# Filter.net
KiCad netlist of a schematic drawn in Altium Designer
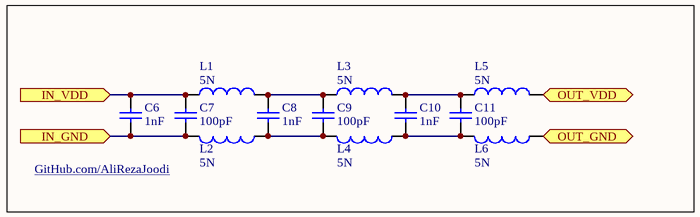
[diagram p0: Filter.SchDoc]

(export (version "E")
  (design (tool "Eeschema 10.0.6"))
  (components
    (comp (ref "C6")
      (value "1nF")
      (footprint "CAPNTO2.54-3.56x2.03")
      (description "Capacitor")
      (fields (field (name "MANUFACTURER") "Generic Components") (field (name "PUBLISHER") "Altium Limited"))
      (libsource (lib "Miscellaneous Devices") (part "Cap"))
    )
    (comp (ref "C7")
      (value "100pF")
      (footprint "CAPNTO2.54-3.56x2.03")
      (description "Capacitor")
      (fields (field (name "MANUFACTURER") "Generic Components") (field (name "PUBLISHER") "Altium Limited"))
      (libsource (lib "Miscellaneous Devices") (part "Cap"))
    )
    (comp (ref "C8")
      (value "1nF")
      (footprint "CAPNTO2.54-3.56x2.03")
      (description "Capacitor")
      (fields (field (name "MANUFACTURER") "Generic Components") (field (name "PUBLISHER") "Altium Limited"))
      (libsource (lib "Miscellaneous Devices") (part "Cap"))
    )
    (comp (ref "C9")
      (value "100pF")
      (footprint "CAPNTO2.54-3.56x2.03")
      (description "Capacitor")
      (fields (field (name "MANUFACTURER") "Generic Components") (field (name "PUBLISHER") "Altium Limited"))
      (libsource (lib "Miscellaneous Devices") (part "Cap"))
    )
    (comp (ref "C10")
      (value "1nF")
      (footprint "CAPNTO2.54-3.56x2.03")
      (description "Capacitor")
      (fields (field (name "MANUFACTURER") "Generic Components") (field (name "PUBLISHER") "Altium Limited"))
      (libsource (lib "Miscellaneous Devices") (part "Cap"))
    )
    (comp (ref "C11")
      (value "100pF")
      (footprint "CAPNTO2.54-3.56x2.03")
      (description "Capacitor")
      (fields (field (name "MANUFACTURER") "Generic Components") (field (name "PUBLISHER") "Altium Limited"))
      (libsource (lib "Miscellaneous Devices") (part "Cap"))
    )
    (comp (ref "L1")
      (value "5N")
      (footprint "CAPPR5-6.3x11")
      (description "Inductor")
      (fields (field (name "MANUFACTURER") "Generic Components") (field (name "PUBLISHER") "Altium Limited"))
      (libsource (lib "my Libraries") (part "Inductor"))
    )
    (comp (ref "L2")
      (value "5N")
      (footprint "CAPPR5-6.3x11")
      (description "Inductor")
      (fields (field (name "MANUFACTURER") "Generic Components") (field (name "PUBLISHER") "Altium Limited"))
      (libsource (lib "") (part "Inductor_1"))
    )
    (comp (ref "L3")
      (value "5N")
      (footprint "CAPPR5-6.3x11")
      (description "Inductor")
      (fields (field (name "MANUFACTURER") "Generic Components") (field (name "PUBLISHER") "Altium Limited"))
      (libsource (lib "my Libraries") (part "Inductor"))
    )
    (comp (ref "L4")
      (value "5N")
      (footprint "CAPPR5-6.3x11")
      (description "Inductor")
      (fields (field (name "MANUFACTURER") "Generic Components") (field (name "PUBLISHER") "Altium Limited"))
      (libsource (lib "") (part "Inductor_1"))
    )
    (comp (ref "L5")
      (value "5N")
      (footprint "CAPPR5-6.3x11")
      (description "Inductor")
      (fields (field (name "MANUFACTURER") "Generic Components") (field (name "PUBLISHER") "Altium Limited"))
      (libsource (lib "my Libraries") (part "Inductor"))
    )
    (comp (ref "L6")
      (value "5N")
      (footprint "CAPPR5-6.3x11")
      (description "Inductor")
      (fields (field (name "MANUFACTURER") "Generic Components") (field (name "PUBLISHER") "Altium Limited"))
      (libsource (lib "") (part "Inductor_1"))
    )
  )
  (nets
    (net (code "1") (name "/IN_GND") (class "Default")
      (node (ref "C6") (pin "1") (pinfunction "1_1") (pintype "passive"))
      (node (ref "C7") (pin "1") (pinfunction "1_1") (pintype "passive"))
      (node (ref "L2") (pin "2") (pinfunction "2_2") (pintype "passive"))
    )
    (net (code "2") (name "/IN_VDD") (class "Default")
      (node (ref "C6") (pin "2") (pinfunction "2_2") (pintype "passive"))
      (node (ref "C7") (pin "2") (pinfunction "2_2") (pintype "passive"))
      (node (ref "L1") (pin "2") (pinfunction "2_2") (pintype "passive"))
    )
    (net (code "3") (name "/OUT_GND") (class "Default")
      (node (ref "L6") (pin "1") (pinfunction "1_1") (pintype "passive"))
    )
    (net (code "4") (name "/OUT_VDD") (class "Default")
      (node (ref "L5") (pin "1") (pinfunction "1_1") (pintype "passive"))
    )
    (net (code "5") (name "Net-(C8-Pad1)") (class "Default")
      (node (ref "C8") (pin "1") (pinfunction "1_1") (pintype "passive"))
      (node (ref "C9") (pin "1") (pinfunction "1_1") (pintype "passive"))
      (node (ref "L2") (pin "1") (pinfunction "1_1") (pintype "passive"))
      (node (ref "L4") (pin "2") (pinfunction "2_2") (pintype "passive"))
    )
    (net (code "6") (name "Net-(C8-Pad2)") (class "Default")
      (node (ref "C8") (pin "2") (pinfunction "2_2") (pintype "passive"))
      (node (ref "C9") (pin "2") (pinfunction "2_2") (pintype "passive"))
      (node (ref "L1") (pin "1") (pinfunction "1_1") (pintype "passive"))
      (node (ref "L3") (pin "2") (pinfunction "2_2") (pintype "passive"))
    )
    (net (code "7") (name "Net-(C10-Pad1)") (class "Default")
      (node (ref "C10") (pin "1") (pinfunction "1_1") (pintype "passive"))
      (node (ref "C11") (pin "1") (pinfunction "1_1") (pintype "passive"))
      (node (ref "L4") (pin "1") (pinfunction "1_1") (pintype "passive"))
      (node (ref "L6") (pin "2") (pinfunction "2_2") (pintype "passive"))
    )
    (net (code "8") (name "Net-(C10-Pad2)") (class "Default")
      (node (ref "C10") (pin "2") (pinfunction "2_2") (pintype "passive"))
      (node (ref "C11") (pin "2") (pinfunction "2_2") (pintype "passive"))
      (node (ref "L3") (pin "1") (pinfunction "1_1") (pintype "passive"))
      (node (ref "L5") (pin "2") (pinfunction "2_2") (pintype "passive"))
    )
  )
)
